# MCU_Board_fNIRS.net
KiCad netlist of a schematic drawn in Altium Designer
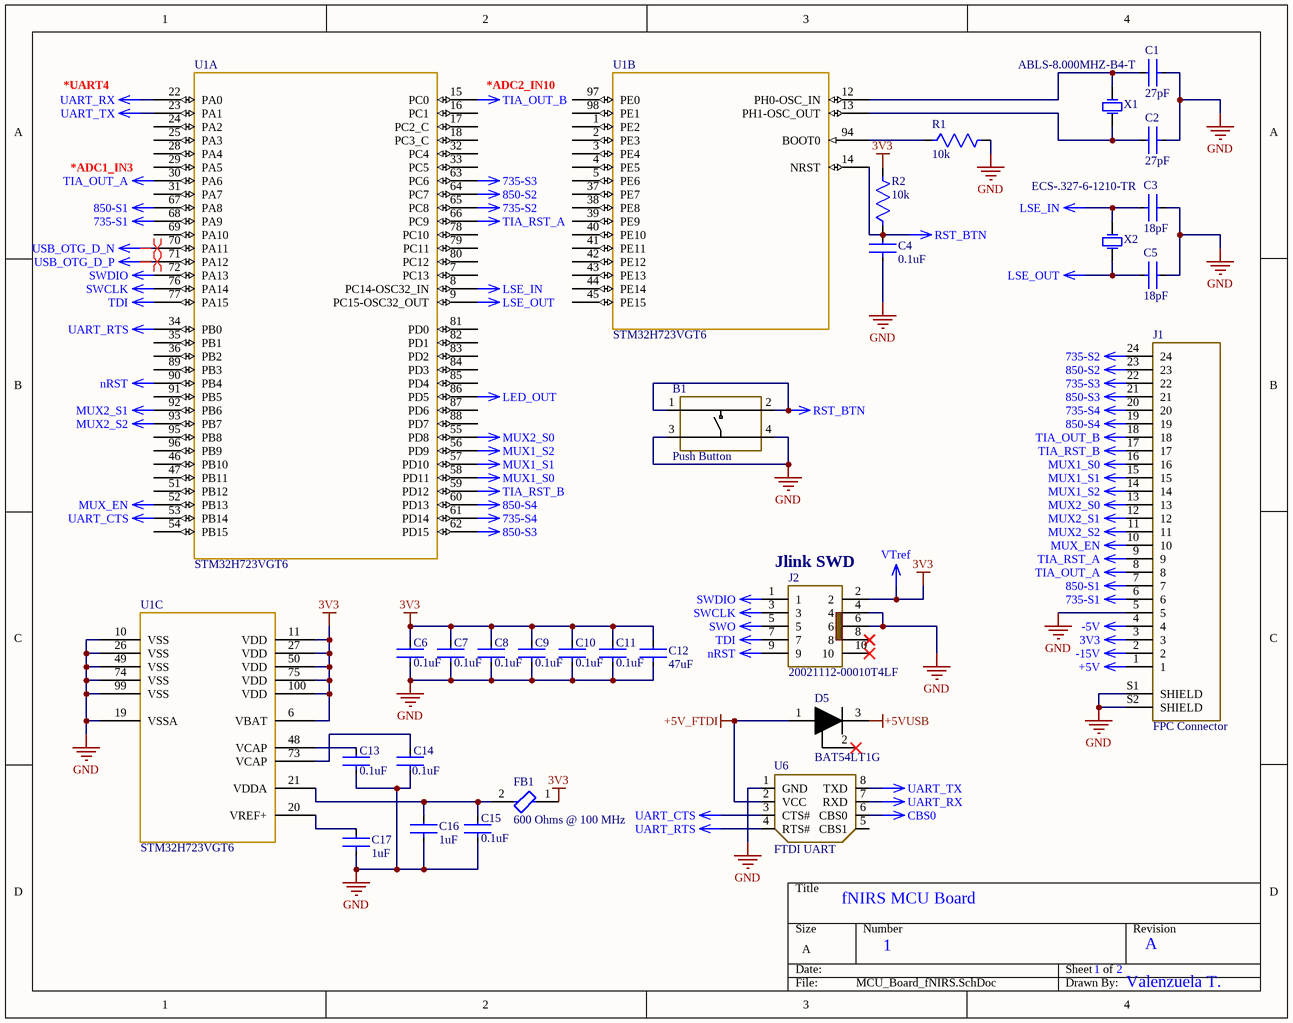
[diagram p0: MCU_Board_fNIRS.SchDoc]

(export (version "E")
  (design (tool "Eeschema 10.0.6"))
  (components
    (comp (ref "B1")
      (value "Push Button")
      (footprint "PTS810")
      (description "Tactile Switch SPST-NO Top Actuated Surface Mount")
      (libsource (lib "MCU_Board_fNIRS") (part "PTS810 SJG 250 SMTR LFS"))
    )
    (comp (ref "C1")
      (value "27pF")
      (footprint "CAPC3216X180N")
      (description "CAP CER 27PF 50V C0G/NP0 1206")
      (fields (field (name "TOLERANCE") "-20% to +80%"))
      (libsource (lib "MCU_Board_fNIRS") (part "C1206C270K5GAC7800"))
    )
    (comp (ref "C2")
      (value "27pF")
      (footprint "CAPC3216X180N")
      (description "CAP CER 27PF 50V C0G/NP0 1206")
      (fields (field (name "TOLERANCE") "-20% to +80%"))
      (libsource (lib "MCU_Board_fNIRS") (part "C1206C270K5GAC7800"))
    )
    (comp (ref "C3")
      (value "18pF")
      (footprint "CAPC3216X180N")
      (description "18 pF ±5% 50V Ceramic Capacitor C0G, NP0 1206 (3216 Metric)")
      (fields (field (name "TOLERANCE") "-20% to +80%"))
      (libsource (lib "MCU_Board_fNIRS") (part "C1206C180J5GAC7800"))
    )
    (comp (ref "C4")
      (value "0.1uF")
      (footprint "CAPC3216X180N")
      (description "1206")
      (fields (field (name "TOLERANCE") "0.1") (field (name "MANUFACTURER") "KEMET"))
      (libsource (lib "Single_Channel_fNIRS") (part "C1206C104K5RAC7210"))
    )
    (comp (ref "C5")
      (value "18pF")
      (footprint "CAPC3216X180N")
      (description "18 pF ±5% 50V Ceramic Capacitor C0G, NP0 1206 (3216 Metric)")
      (fields (field (name "TOLERANCE") "-20% to +80%"))
      (libsource (lib "MCU_Board_fNIRS") (part "C1206C180J5GAC7800"))
    )
    (comp (ref "C6")
      (value "0.1uF")
      (footprint "CAPC3216X180N")
      (description "1206")
      (fields (field (name "TOLERANCE") "0.1") (field (name "MANUFACTURER") "KEMET"))
      (libsource (lib "Single_Channel_fNIRS") (part "C1206C104K5RAC7210"))
    )
    (comp (ref "C7")
      (value "0.1uF")
      (footprint "CAPC3216X180N")
      (description "1206")
      (fields (field (name "TOLERANCE") "0.1") (field (name "MANUFACTURER") "KEMET"))
      (libsource (lib "Single_Channel_fNIRS") (part "C1206C104K5RAC7210"))
    )
    (comp (ref "C8")
      (value "0.1uF")
      (footprint "CAPC3216X180N")
      (description "1206")
      (fields (field (name "TOLERANCE") "0.1") (field (name "MANUFACTURER") "KEMET"))
      (libsource (lib "Single_Channel_fNIRS") (part "C1206C104K5RAC7210"))
    )
    (comp (ref "C9")
      (value "0.1uF")
      (footprint "CAPC3216X180N")
      (description "1206")
      (fields (field (name "TOLERANCE") "0.1") (field (name "MANUFACTURER") "KEMET"))
      (libsource (lib "Single_Channel_fNIRS") (part "C1206C104K5RAC7210"))
    )
    (comp (ref "C10")
      (value "0.1uF")
      (footprint "CAPC3216X180N")
      (description "1206")
      (fields (field (name "TOLERANCE") "0.1") (field (name "MANUFACTURER") "KEMET"))
      (libsource (lib "Single_Channel_fNIRS") (part "C1206C104K5RAC7210"))
    )
    (comp (ref "C11")
      (value "0.1uF")
      (footprint "CAPC3216X180N")
      (description "1206")
      (fields (field (name "TOLERANCE") "0.1") (field (name "MANUFACTURER") "KEMET"))
      (libsource (lib "Single_Channel_fNIRS") (part "C1206C104K5RAC7210"))
    )
    (comp (ref "C12")
      (value "47uF")
      (footprint "CAPC3216X180N")
      (description "47 µF ±20% 6.3V Ceramic Capacitor X5R 1206 (3216 Metric)")
      (fields (field (name "TOLERANCE") "-20% to +80%"))
      (libsource (lib "MCU_Board_fNIRS") (part "CL31A476MQHNNWE"))
    )
    (comp (ref "C13")
      (value "0.1uF")
      (footprint "CAPC3216X180N")
      (description "1206")
      (fields (field (name "TOLERANCE") "0.1") (field (name "MANUFACTURER") "KEMET"))
      (libsource (lib "Single_Channel_fNIRS") (part "C1206C104K5RAC7210"))
    )
    (comp (ref "C14")
      (value "0.1uF")
      (footprint "CAPC3216X180N")
      (description "1206")
      (fields (field (name "TOLERANCE") "0.1") (field (name "MANUFACTURER") "KEMET"))
      (libsource (lib "Single_Channel_fNIRS") (part "C1206C104K5RAC7210"))
    )
    (comp (ref "C15")
      (value "0.1uF")
      (footprint "CAPC3216X180N")
      (description "1206")
      (fields (field (name "TOLERANCE") "0.1") (field (name "MANUFACTURER") "KEMET"))
      (libsource (lib "Single_Channel_fNIRS") (part "C1206C104K5RAC7210"))
    )
    (comp (ref "C16")
      (value "1uF")
      (footprint "CAPC1206(3216)130_M")
      (description "CAP 1uF 25V -20% to +80% 1206 (3216 Metric) Thickness 1.3mm SMD\r\nC1206C105Z3VAC7800")
      (fields (field (name "TOLERANCE") "-20% to +80%"))
      (libsource (lib "MCU_Board_fNIRS") (part "12063G105ZAT4A_1"))
    )
    (comp (ref "C17")
      (value "1uF")
      (footprint "CAPC1206(3216)130_M")
      (description "CAP 1uF 25V -20% to +80% 1206 (3216 Metric) Thickness 1.3mm SMD")
      (fields (field (name "TOLERANCE") "-20% to +80%"))
      (libsource (lib "MCU_Board_fNIRS") (part "12063G105ZAT4A_1"))
    )
    (comp (ref "D5")
      (value "BAT54LT1G")
      (footprint "BAT54LT1")
      (description "Schottky Barrier Diode, 3-Pin SOT-23, Pb-Free, Tape and Reel")
      (fields (field (name "MANUFACTURER") "On Semiconductor"))
      (libsource (lib "Single_Channel_fNIRS") (part "BAT54L"))
    )
    (comp (ref "FB1")
      (value "600 Ohms @ 100 MHz")
      (footprint "BEADC1608X95N")
      (description "600 Ohms @ 100 MHz 1 Ferrite Bead 0603 (1608 Metric) 350mA 500mOhm")
      (fields (field (name "TOLERANCE") "-20% to +80%"))
      (libsource (lib "MCU_Board_fNIRS") (part "FCM 1608KF-601T03"))
    )
    (comp (ref "J1")
      (value "FPC Connector")
      (footprint "TE_FPC")
      (description "24 Position FPC Connector Contacts, Bottom 0.020\" _0.50mm_ Surface Mount, Right Angle")
      (fields (field (name "MP") "2-1734592-4") (field (name "MF") "TE Connectivity"))
      (libsource (lib "MCU_Board_fNIRS") (part "2-1734592-4"))
    )
    (comp (ref "J2")
      (value "20021112-00010T4LF")
      (footprint "AMPHENOL_20021112-00010T4LF")
      (description "Connector Header Through Hole, Right Angle 10 position 0.050\" (1.27mm)")
      (fields (field (name "MF") "Amphenol"))
      (libsource (lib "MCU_Board_fNIRS") (part "20021112-00010T4LF"))
    )
    (comp (ref "R1")
      (value "10k")
      (footprint "R1206")
      (description "1206 10kOhm")
      (libsource (lib "MCU_Board_fNIRS") (part "RC1206FR-0710KL"))
    )
    (comp (ref "R2")
      (value "10k")
      (footprint "R1206")
      (description "1206 10kOhm")
      (libsource (lib "MCU_Board_fNIRS") (part "RC1206FR-0710KL"))
    )
    (comp (ref "U1")
      (value "STM32H723VGT6")
      (footprint "LQFP100_STM")
      (description "No Description Available")
      (libsource (lib "MCU_Board_fNIRS") (part "STM32H723VGT6"))
    )
    (comp (ref "U6")
      (value "FTDI UART")
      (footprint "UB232R")
      (description "FT232R - USB 2.0 to UART (RS232) Bridge Interface Evaluation Board")
      (libsource (lib "MCU_Board_fNIRS") (part "UB232R"))
    )
    (comp (ref "X1")
      (value "ABLS-8.000MHZ-B4-T")
      (footprint "ABRA-ABLS-14.7456MHZ-B2-T_V")
      (description "Low Profile Crystal, 8.0 MHz, +/- 30 ppm, -20 to 70 degC, 2-Pin SMD, RoHS, Tape and Reel")
      (fields (field (name "MANUFACTURER") "ABRACON") (field (name "TOLERANCE") "30PPM"))
      (libsource (lib "MCU_Board_fNIRS") (part "ABLS-8.000MHZ-B4-T"))
    )
    (comp (ref "X2")
      (value "ECS-.327-6-1210-TR")
      (footprint "ECS-.327-6-1210-TR")
      (description "Low Profile Crystal, 8.0 MHz, +/- 30 ppm, -20 to 70 degC, 2-Pin SMD, RoHS, Tape and Reel")
      (fields (field (name "MANUFACTURER") "ABRACON") (field (name "TOLERANCE") "30PPM"))
      (libsource (lib "MCU_Board_fNIRS") (part "ECS-.327-6-1210-TR"))
    )
  )
  (nets
    (net (code "1") (name "+5V") (class "Default")
      (node (ref "J1") (pin "1") (pinfunction "1_1") (pintype "passive"))
    )
    (net (code "2") (name "+5VUSB") (class "Default")
      (node (ref "D5") (pin "3") (pinfunction "K_3") (pintype "passive"))
    )
    (net (code "3") (name "+5V_FTDI") (class "Default")
      (node (ref "D5") (pin "1") (pinfunction "A_1") (pintype "passive"))
      (node (ref "U6") (pin "2") (pinfunction "VCC_2") (pintype "passive"))
    )
    (net (code "4") (name "-5V") (class "Default")
      (node (ref "J1") (pin "4") (pinfunction "4_4") (pintype "passive"))
    )
    (net (code "5") (name "-15V") (class "Default")
      (node (ref "J1") (pin "2") (pinfunction "2_2") (pintype "passive"))
    )
    (net (code "6") (name "3V3") (class "Default")
      (node (ref "C10") (pin "2") (pinfunction "2_2") (pintype "passive"))
      (node (ref "C11") (pin "2") (pinfunction "2_2") (pintype "passive"))
      (node (ref "C12") (pin "2") (pinfunction "2_2") (pintype "passive"))
      (node (ref "C6") (pin "2") (pinfunction "2_2") (pintype "passive"))
      (node (ref "C7") (pin "2") (pinfunction "2_2") (pintype "passive"))
      (node (ref "C8") (pin "2") (pinfunction "2_2") (pintype "passive"))
      (node (ref "C9") (pin "2") (pinfunction "2_2") (pintype "passive"))
      (node (ref "FB1") (pin "1") (pinfunction "1_1") (pintype "passive"))
      (node (ref "J1") (pin "3") (pinfunction "3_3") (pintype "passive"))
      (node (ref "J2") (pin "2") (pinfunction "2_2") (pintype "passive"))
      (node (ref "R2") (pin "2") (pinfunction "2_2") (pintype "passive"))
      (node (ref "U1") (pin "100") (pinfunction "VDD_100") (pintype "power_in"))
      (node (ref "U1") (pin "11") (pinfunction "VDD_11") (pintype "power_in"))
      (node (ref "U1") (pin "27") (pinfunction "VDD_27") (pintype "power_in"))
      (node (ref "U1") (pin "50") (pinfunction "VDD_50") (pintype "power_in"))
      (node (ref "U1") (pin "6") (pinfunction "VBAT_6") (pintype "power_in"))
      (node (ref "U1") (pin "75") (pinfunction "VDD_75") (pintype "power_in"))
    )
    (net (code "7") (name "735-S1") (class "Default")
      (node (ref "J1") (pin "6") (pinfunction "6_6") (pintype "passive"))
      (node (ref "U1") (pin "68") (pinfunction "PA9_68") (pintype "bidirectional"))
    )
    (net (code "8") (name "735-S2") (class "Default")
      (node (ref "J1") (pin "24") (pinfunction "24_24") (pintype "passive"))
      (node (ref "U1") (pin "65") (pinfunction "PC8_65") (pintype "bidirectional"))
    )
    (net (code "9") (name "735-S3") (class "Default")
      (node (ref "J1") (pin "22") (pinfunction "22_22") (pintype "passive"))
      (node (ref "U1") (pin "63") (pinfunction "PC6_63") (pintype "bidirectional"))
    )
    (net (code "10") (name "735-S4") (class "Default")
      (node (ref "J1") (pin "20") (pinfunction "20_20") (pintype "passive"))
      (node (ref "U1") (pin "61") (pinfunction "PD14_61") (pintype "bidirectional"))
    )
    (net (code "11") (name "850-S1") (class "Default")
      (node (ref "J1") (pin "7") (pinfunction "7_7") (pintype "passive"))
      (node (ref "U1") (pin "67") (pinfunction "PA8_67") (pintype "bidirectional"))
    )
    (net (code "12") (name "850-S2") (class "Default")
      (node (ref "J1") (pin "23") (pinfunction "23_23") (pintype "passive"))
      (node (ref "U1") (pin "64") (pinfunction "PC7_64") (pintype "bidirectional"))
    )
    (net (code "13") (name "850-S3") (class "Default")
      (node (ref "J1") (pin "21") (pinfunction "21_21") (pintype "passive"))
      (node (ref "U1") (pin "62") (pinfunction "PD15_62") (pintype "bidirectional"))
    )
    (net (code "14") (name "850-S4") (class "Default")
      (node (ref "J1") (pin "19") (pinfunction "19_19") (pintype "passive"))
      (node (ref "U1") (pin "60") (pinfunction "PD13_60") (pintype "bidirectional"))
    )
    (net (code "15") (name "CBS0") (class "Default")
      (node (ref "U6") (pin "6") (pinfunction "CBS0_6") (pintype "passive"))
    )
    (net (code "16") (name "GND") (class "Default")
      (node (ref "B1") (pin "3") (pinfunction "3_3") (pintype "passive"))
      (node (ref "B1") (pin "4") (pinfunction "4_4") (pintype "passive"))
      (node (ref "C1") (pin "1") (pinfunction "1_1") (pintype "passive"))
      (node (ref "C10") (pin "1") (pinfunction "1_1") (pintype "passive"))
      (node (ref "C11") (pin "1") (pinfunction "1_1") (pintype "passive"))
      (node (ref "C12") (pin "1") (pinfunction "1_1") (pintype "passive"))
      (node (ref "C13") (pin "1") (pinfunction "1_1") (pintype "passive"))
      (node (ref "C14") (pin "1") (pinfunction "1_1") (pintype "passive"))
      (node (ref "C15") (pin "1") (pinfunction "1_1") (pintype "passive"))
      (node (ref "C16") (pin "1") (pinfunction "1_1") (pintype "passive"))
      (node (ref "C17") (pin "1") (pinfunction "1_1") (pintype "passive"))
      (node (ref "C2") (pin "1") (pinfunction "1_1") (pintype "passive"))
      (node (ref "C3") (pin "2") (pinfunction "2_2") (pintype "passive"))
      (node (ref "C4") (pin "1") (pinfunction "1_1") (pintype "passive"))
      (node (ref "C5") (pin "2") (pinfunction "2_2") (pintype "passive"))
      (node (ref "C6") (pin "1") (pinfunction "1_1") (pintype "passive"))
      (node (ref "C7") (pin "1") (pinfunction "1_1") (pintype "passive"))
      (node (ref "C8") (pin "1") (pinfunction "1_1") (pintype "passive"))
      (node (ref "C9") (pin "1") (pinfunction "1_1") (pintype "passive"))
      (node (ref "J1") (pin "5") (pinfunction "5_5") (pintype "passive"))
      (node (ref "J1") (pin "S1") (pinfunction "SHIELD_S1") (pintype "passive"))
      (node (ref "J1") (pin "S2") (pinfunction "SHIELD_S2") (pintype "passive"))
      (node (ref "J2") (pin "4") (pinfunction "4_4") (pintype "passive"))
      (node (ref "J2") (pin "6") (pinfunction "6_6") (pintype "passive"))
      (node (ref "R1") (pin "2") (pinfunction "2_2") (pintype "passive"))
      (node (ref "U1") (pin "10") (pinfunction "VSS_10") (pintype "power_in"))
      (node (ref "U1") (pin "19") (pinfunction "VSSA_19") (pintype "power_in"))
      (node (ref "U1") (pin "26") (pinfunction "VSS_26") (pintype "power_in"))
      (node (ref "U1") (pin "49") (pinfunction "VSS_49") (pintype "power_in"))
      (node (ref "U1") (pin "74") (pinfunction "VSS_74") (pintype "power_in"))
      (node (ref "U1") (pin "99") (pinfunction "VSS_99") (pintype "power_in"))
      (node (ref "U6") (pin "1") (pinfunction "GND_1") (pintype "passive"))
    )
    (net (code "17") (name "LED_OUT") (class "Default")
      (node (ref "U1") (pin "86") (pinfunction "PD5_86") (pintype "bidirectional"))
    )
    (net (code "18") (name "LSE_IN") (class "Default")
      (node (ref "C3") (pin "1") (pinfunction "1_1") (pintype "passive"))
      (node (ref "U1") (pin "8") (pinfunction "PC14-OSC32_IN_8") (pintype "bidirectional"))
      (node (ref "X2") (pin "2") (pinfunction "X2_2") (pintype "passive"))
    )
    (net (code "19") (name "LSE_OUT") (class "Default")
      (node (ref "C5") (pin "1") (pinfunction "1_1") (pintype "passive"))
      (node (ref "U1") (pin "9") (pinfunction "PC15-OSC32_OUT_9") (pintype "bidirectional"))
      (node (ref "X2") (pin "1") (pinfunction "X1_1") (pintype "passive"))
    )
    (net (code "20") (name "MUX1_S0") (class "Default")
      (node (ref "J1") (pin "16") (pinfunction "16_16") (pintype "passive"))
      (node (ref "U1") (pin "58") (pinfunction "PD11_58") (pintype "bidirectional"))
    )
    (net (code "21") (name "MUX1_S1") (class "Default")
      (node (ref "J1") (pin "15") (pinfunction "15_15") (pintype "passive"))
      (node (ref "U1") (pin "57") (pinfunction "PD10_57") (pintype "bidirectional"))
    )
    (net (code "22") (name "MUX1_S2") (class "Default")
      (node (ref "J1") (pin "14") (pinfunction "14_14") (pintype "passive"))
      (node (ref "U1") (pin "56") (pinfunction "PD9_56") (pintype "bidirectional"))
    )
    (net (code "23") (name "MUX2_S0") (class "Default")
      (node (ref "J1") (pin "13") (pinfunction "13_13") (pintype "passive"))
      (node (ref "U1") (pin "55") (pinfunction "PD8_55") (pintype "bidirectional"))
    )
    (net (code "24") (name "MUX2_S1") (class "Default")
      (node (ref "J1") (pin "12") (pinfunction "12_12") (pintype "passive"))
      (node (ref "U1") (pin "92") (pinfunction "PB6_92") (pintype "bidirectional"))
    )
    (net (code "25") (name "MUX2_S2") (class "Default")
      (node (ref "J1") (pin "11") (pinfunction "11_11") (pintype "passive"))
      (node (ref "U1") (pin "93") (pinfunction "PB7_93") (pintype "bidirectional"))
    )
    (net (code "26") (name "MUX_EN") (class "Default")
      (node (ref "J1") (pin "10") (pinfunction "10_10") (pintype "passive"))
      (node (ref "U1") (pin "52") (pinfunction "PB13_52") (pintype "bidirectional"))
    )
    (net (code "27") (name "Net-(C13-Pad2)") (class "Default")
      (node (ref "C13") (pin "2") (pinfunction "2_2") (pintype "passive"))
      (node (ref "U1") (pin "48") (pinfunction "VCAP_48") (pintype "power_in"))
    )
    (net (code "28") (name "Net-(C14-Pad2)") (class "Default")
      (node (ref "C14") (pin "2") (pinfunction "2_2") (pintype "passive"))
      (node (ref "U1") (pin "73") (pinfunction "VCAP_73") (pintype "power_in"))
    )
    (net (code "29") (name "Net-(U1B-BOOT0)") (class "Default")
      (node (ref "R1") (pin "1") (pinfunction "1_1") (pintype "passive"))
      (node (ref "U1") (pin "94") (pinfunction "BOOT0_94") (pintype "input"))
    )
    (net (code "30") (name "Net-(U1B-PH0-OSC_IN)") (class "Default")
      (node (ref "C1") (pin "2") (pinfunction "2_2") (pintype "passive"))
      (node (ref "U1") (pin "12") (pinfunction "PH0-OSC_IN_12") (pintype "bidirectional"))
      (node (ref "X1") (pin "1") (pinfunction "X1_1") (pintype "passive"))
    )
    (net (code "31") (name "Net-(U1B-PH1-OSC_OUT)") (class "Default")
      (node (ref "C2") (pin "2") (pinfunction "2_2") (pintype "passive"))
      (node (ref "U1") (pin "13") (pinfunction "PH1-OSC_OUT_13") (pintype "bidirectional"))
      (node (ref "X1") (pin "2") (pinfunction "X2_2") (pintype "passive"))
    )
    (net (code "32") (name "Net-(U1C-VDDA)") (class "Default")
      (node (ref "C15") (pin "2") (pinfunction "2_2") (pintype "passive"))
      (node (ref "C16") (pin "2") (pinfunction "2_2") (pintype "passive"))
      (node (ref "FB1") (pin "2") (pinfunction "2_2") (pintype "passive"))
      (node (ref "U1") (pin "21") (pinfunction "VDDA_21") (pintype "power_in"))
    )
    (net (code "33") (name "Net-(U1C-VREF+)") (class "Default")
      (node (ref "C17") (pin "2") (pinfunction "2_2") (pintype "passive"))
      (node (ref "U1") (pin "20") (pinfunction "VREF+_20") (pintype "power_in"))
    )
    (net (code "34") (name "RST_BTN") (class "Default")
      (node (ref "B1") (pin "1") (pinfunction "1_1") (pintype "passive"))
      (node (ref "B1") (pin "2") (pinfunction "2_2") (pintype "passive"))
      (node (ref "C4") (pin "2") (pinfunction "2_2") (pintype "passive"))
      (node (ref "R2") (pin "1") (pinfunction "1_1") (pintype "passive"))
      (node (ref "U1") (pin "14") (pinfunction "NRST_14") (pintype "bidirectional"))
    )
    (net (code "35") (name "SWCLK") (class "Default")
      (node (ref "J2") (pin "3") (pinfunction "3_3") (pintype "passive"))
      (node (ref "U1") (pin "76") (pinfunction "PA14_76") (pintype "bidirectional"))
    )
    (net (code "36") (name "SWDIO") (class "Default")
      (node (ref "J2") (pin "1") (pinfunction "1_1") (pintype "passive"))
      (node (ref "U1") (pin "72") (pinfunction "PA13_72") (pintype "bidirectional"))
    )
    (net (code "37") (name "SWO") (class "Default")
      (node (ref "J2") (pin "5") (pinfunction "5_5") (pintype "passive"))
    )
    (net (code "38") (name "TDI") (class "Default")
      (node (ref "J2") (pin "7") (pinfunction "7_7") (pintype "passive"))
      (node (ref "U1") (pin "77") (pinfunction "PA15_77") (pintype "bidirectional"))
    )
    (net (code "39") (name "TIA_OUT_A") (class "Default")
      (node (ref "J1") (pin "8") (pinfunction "8_8") (pintype "passive"))
      (node (ref "U1") (pin "30") (pinfunction "PA6_30") (pintype "bidirectional"))
    )
    (net (code "40") (name "TIA_OUT_B") (class "Default")
      (node (ref "J1") (pin "18") (pinfunction "18_18") (pintype "passive"))
      (node (ref "U1") (pin "15") (pinfunction "PC0_15") (pintype "bidirectional"))
    )
    (net (code "41") (name "TIA_RST_A") (class "Default")
      (node (ref "J1") (pin "9") (pinfunction "9_9") (pintype "passive"))
      (node (ref "U1") (pin "66") (pinfunction "PC9_66") (pintype "bidirectional"))
    )
    (net (code "42") (name "TIA_RST_B") (class "Default")
      (node (ref "J1") (pin "17") (pinfunction "17_17") (pintype "passive"))
      (node (ref "U1") (pin "59") (pinfunction "PD12_59") (pintype "bidirectional"))
    )
    (net (code "43") (name "UART_CTS") (class "Default")
      (node (ref "U1") (pin "53") (pinfunction "PB14_53") (pintype "bidirectional"))
      (node (ref "U6") (pin "3") (pinfunction "CTS#_3") (pintype "passive"))
    )
    (net (code "44") (name "UART_RTS") (class "Default")
      (node (ref "U1") (pin "34") (pinfunction "PB0_34") (pintype "bidirectional"))
      (node (ref "U6") (pin "4") (pinfunction "RTS#_4") (pintype "passive"))
    )
    (net (code "45") (name "UART_RX") (class "Default")
      (node (ref "U1") (pin "22") (pinfunction "PA0_22") (pintype "bidirectional"))
      (node (ref "U6") (pin "7") (pinfunction "RXD_7") (pintype "passive"))
    )
    (net (code "46") (name "UART_TX") (class "Default")
      (node (ref "U1") (pin "23") (pinfunction "PA1_23") (pintype "bidirectional"))
      (node (ref "U6") (pin "8") (pinfunction "TXD_8") (pintype "passive"))
    )
    (net (code "47") (name "USB_OTG_D_N") (class "Default")
      (node (ref "U1") (pin "70") (pinfunction "PA11_70") (pintype "bidirectional"))
    )
    (net (code "48") (name "USB_OTG_D_P") (class "Default")
      (node (ref "U1") (pin "71") (pinfunction "PA12_71") (pintype "bidirectional"))
    )
    (net (code "49") (name "nRST") (class "Default")
      (node (ref "J2") (pin "9") (pinfunction "9_9") (pintype "passive"))
      (node (ref "U1") (pin "90") (pinfunction "PB4_90") (pintype "bidirectional"))
    )
    (net (code "50") (name "unconnected-(D5-NC-Pad2)") (class "Default")
      (node (ref "D5") (pin "2") (pinfunction "NC_2") (pintype "passive+no_connect"))
    )
    (net (code "51") (name "unconnected-(J2-Pad8)") (class "Default")
      (node (ref "J2") (pin "8") (pinfunction "8_8") (pintype "passive+no_connect"))
    )
    (net (code "52") (name "unconnected-(J2-Pad10)") (class "Default")
      (node (ref "J2") (pin "10") (pinfunction "10_10") (pintype "passive+no_connect"))
    )
    (net (code "53") (name "unconnected-(U1A-PA2-Pad24)") (class "Default")
      (node (ref "U1") (pin "24") (pinfunction "PA2_24") (pintype "bidirectional"))
    )
    (net (code "54") (name "unconnected-(U1A-PA3-Pad25)") (class "Default")
      (node (ref "U1") (pin "25") (pinfunction "PA3_25") (pintype "bidirectional"))
    )
    (net (code "55") (name "unconnected-(U1A-PA4-Pad28)") (class "Default")
      (node (ref "U1") (pin "28") (pinfunction "PA4_28") (pintype "bidirectional"))
    )
    (net (code "56") (name "unconnected-(U1A-PA5-Pad29)") (class "Default")
      (node (ref "U1") (pin "29") (pinfunction "PA5_29") (pintype "bidirectional"))
    )
    (net (code "57") (name "unconnected-(U1A-PA7-Pad31)") (class "Default")
      (node (ref "U1") (pin "31") (pinfunction "PA7_31") (pintype "bidirectional"))
    )
    (net (code "58") (name "unconnected-(U1A-PA10-Pad69)") (class "Default")
      (node (ref "U1") (pin "69") (pinfunction "PA10_69") (pintype "bidirectional"))
    )
    (net (code "59") (name "unconnected-(U1A-PB1-Pad35)") (class "Default")
      (node (ref "U1") (pin "35") (pinfunction "PB1_35") (pintype "bidirectional"))
    )
    (net (code "60") (name "unconnected-(U1A-PB2-Pad36)") (class "Default")
      (node (ref "U1") (pin "36") (pinfunction "PB2_36") (pintype "bidirectional"))
    )
    (net (code "61") (name "unconnected-(U1A-PB3-Pad89)") (class "Default")
      (node (ref "U1") (pin "89") (pinfunction "PB3_89") (pintype "bidirectional"))
    )
    (net (code "62") (name "unconnected-(U1A-PB5-Pad91)") (class "Default")
      (node (ref "U1") (pin "91") (pinfunction "PB5_91") (pintype "bidirectional"))
    )
    (net (code "63") (name "unconnected-(U1A-PB8-Pad95)") (class "Default")
      (node (ref "U1") (pin "95") (pinfunction "PB8_95") (pintype "bidirectional"))
    )
    (net (code "64") (name "unconnected-(U1A-PB9-Pad96)") (class "Default")
      (node (ref "U1") (pin "96") (pinfunction "PB9_96") (pintype "bidirectional"))
    )
    (net (code "65") (name "unconnected-(U1A-PB10-Pad46)") (class "Default")
      (node (ref "U1") (pin "46") (pinfunction "PB10_46") (pintype "bidirectional"))
    )
    (net (code "66") (name "unconnected-(U1A-PB11-Pad47)") (class "Default")
      (node (ref "U1") (pin "47") (pinfunction "PB11_47") (pintype "bidirectional"))
    )
    (net (code "67") (name "unconnected-(U1A-PB12-Pad51)") (class "Default")
      (node (ref "U1") (pin "51") (pinfunction "PB12_51") (pintype "bidirectional"))
    )
    (net (code "68") (name "unconnected-(U1A-PB15-Pad54)") (class "Default")
      (node (ref "U1") (pin "54") (pinfunction "PB15_54") (pintype "bidirectional"))
    )
    (net (code "69") (name "unconnected-(U1A-PC1-Pad16)") (class "Default")
      (node (ref "U1") (pin "16") (pinfunction "PC1_16") (pintype "bidirectional"))
    )
    (net (code "70") (name "unconnected-(U1A-PC2_C-Pad17)") (class "Default")
      (node (ref "U1") (pin "17") (pinfunction "PC2_C_17") (pintype "bidirectional"))
    )
    (net (code "71") (name "unconnected-(U1A-PC3_C-Pad18)") (class "Default")
      (node (ref "U1") (pin "18") (pinfunction "PC3_C_18") (pintype "bidirectional"))
    )
    (net (code "72") (name "unconnected-(U1A-PC4-Pad32)") (class "Default")
      (node (ref "U1") (pin "32") (pinfunction "PC4_32") (pintype "bidirectional"))
    )
    (net (code "73") (name "unconnected-(U1A-PC5-Pad33)") (class "Default")
      (node (ref "U1") (pin "33") (pinfunction "PC5_33") (pintype "bidirectional"))
    )
    (net (code "74") (name "unconnected-(U1A-PC10-Pad78)") (class "Default")
      (node (ref "U1") (pin "78") (pinfunction "PC10_78") (pintype "bidirectional"))
    )
    (net (code "75") (name "unconnected-(U1A-PC11-Pad79)") (class "Default")
      (node (ref "U1") (pin "79") (pinfunction "PC11_79") (pintype "bidirectional"))
    )
    (net (code "76") (name "unconnected-(U1A-PC12-Pad80)") (class "Default")
      (node (ref "U1") (pin "80") (pinfunction "PC12_80") (pintype "bidirectional"))
    )
    (net (code "77") (name "unconnected-(U1A-PC13-Pad7)") (class "Default")
      (node (ref "U1") (pin "7") (pinfunction "PC13_7") (pintype "bidirectional"))
    )
    (net (code "78") (name "unconnected-(U1A-PD0-Pad81)") (class "Default")
      (node (ref "U1") (pin "81") (pinfunction "PD0_81") (pintype "bidirectional"))
    )
    (net (code "79") (name "unconnected-(U1A-PD1-Pad82)") (class "Default")
      (node (ref "U1") (pin "82") (pinfunction "PD1_82") (pintype "bidirectional"))
    )
    (net (code "80") (name "unconnected-(U1A-PD2-Pad83)") (class "Default")
      (node (ref "U1") (pin "83") (pinfunction "PD2_83") (pintype "bidirectional"))
    )
    (net (code "81") (name "unconnected-(U1A-PD3-Pad84)") (class "Default")
      (node (ref "U1") (pin "84") (pinfunction "PD3_84") (pintype "bidirectional"))
    )
    (net (code "82") (name "unconnected-(U1A-PD4-Pad85)") (class "Default")
      (node (ref "U1") (pin "85") (pinfunction "PD4_85") (pintype "bidirectional"))
    )
    (net (code "83") (name "unconnected-(U1A-PD6-Pad87)") (class "Default")
      (node (ref "U1") (pin "87") (pinfunction "PD6_87") (pintype "bidirectional"))
    )
    (net (code "84") (name "unconnected-(U1A-PD7-Pad88)") (class "Default")
      (node (ref "U1") (pin "88") (pinfunction "PD7_88") (pintype "bidirectional"))
    )
    (net (code "85") (name "unconnected-(U1B-PE0-Pad97)") (class "Default")
      (node (ref "U1") (pin "97") (pinfunction "PE0_97") (pintype "bidirectional"))
    )
    (net (code "86") (name "unconnected-(U1B-PE1-Pad98)") (class "Default")
      (node (ref "U1") (pin "98") (pinfunction "PE1_98") (pintype "bidirectional"))
    )
    (net (code "87") (name "unconnected-(U1B-PE2-Pad1)") (class "Default")
      (node (ref "U1") (pin "1") (pinfunction "PE2_1") (pintype "bidirectional"))
    )
    (net (code "88") (name "unconnected-(U1B-PE3-Pad2)") (class "Default")
      (node (ref "U1") (pin "2") (pinfunction "PE3_2") (pintype "bidirectional"))
    )
    (net (code "89") (name "unconnected-(U1B-PE4-Pad3)") (class "Default")
      (node (ref "U1") (pin "3") (pinfunction "PE4_3") (pintype "bidirectional"))
    )
    (net (code "90") (name "unconnected-(U1B-PE5-Pad4)") (class "Default")
      (node (ref "U1") (pin "4") (pinfunction "PE5_4") (pintype "bidirectional"))
    )
    (net (code "91") (name "unconnected-(U1B-PE6-Pad5)") (class "Default")
      (node (ref "U1") (pin "5") (pinfunction "PE6_5") (pintype "bidirectional"))
    )
    (net (code "92") (name "unconnected-(U1B-PE7-Pad37)") (class "Default")
      (node (ref "U1") (pin "37") (pinfunction "PE7_37") (pintype "bidirectional"))
    )
    (net (code "93") (name "unconnected-(U1B-PE8-Pad38)") (class "Default")
      (node (ref "U1") (pin "38") (pinfunction "PE8_38") (pintype "bidirectional"))
    )
    (net (code "94") (name "unconnected-(U1B-PE9-Pad39)") (class "Default")
      (node (ref "U1") (pin "39") (pinfunction "PE9_39") (pintype "bidirectional"))
    )
    (net (code "95") (name "unconnected-(U1B-PE10-Pad40)") (class "Default")
      (node (ref "U1") (pin "40") (pinfunction "PE10_40") (pintype "bidirectional"))
    )
    (net (code "96") (name "unconnected-(U1B-PE11-Pad41)") (class "Default")
      (node (ref "U1") (pin "41") (pinfunction "PE11_41") (pintype "bidirectional"))
    )
    (net (code "97") (name "unconnected-(U1B-PE12-Pad42)") (class "Default")
      (node (ref "U1") (pin "42") (pinfunction "PE12_42") (pintype "bidirectional"))
    )
    (net (code "98") (name "unconnected-(U1B-PE13-Pad43)") (class "Default")
      (node (ref "U1") (pin "43") (pinfunction "PE13_43") (pintype "bidirectional"))
    )
    (net (code "99") (name "unconnected-(U1B-PE14-Pad44)") (class "Default")
      (node (ref "U1") (pin "44") (pinfunction "PE14_44") (pintype "bidirectional"))
    )
    (net (code "100") (name "unconnected-(U1B-PE15-Pad45)") (class "Default")
      (node (ref "U1") (pin "45") (pinfunction "PE15_45") (pintype "bidirectional"))
    )
    (net (code "101") (name "unconnected-(U6-CBS1-Pad5)") (class "Default")
      (node (ref "U6") (pin "5") (pinfunction "CBS1_5") (pintype "passive"))
    )
  )
)
